# RHS_FEST22-EV_Power.net
KiCad netlist of a schematic drawn in Altium Designer
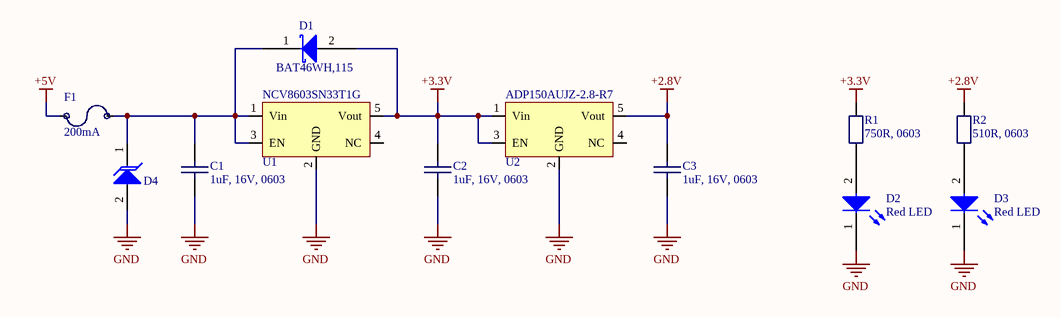
[diagram p0: RHS_FEST22-EV_Power.SchDoc]

(export (version "E")
  (design (tool "Eeschema 10.0.6"))
  (components
    (comp (ref "C1")
      (value "1uF, 16V, 0603")
      (footprint "CAP [0603] 1608")
      (fields (field (name "MANUFACTURER") "MURATA"))
      (libsource (lib "RHS_FEST22-EV_Components") (part "Cap 1uF"))
    )
    (comp (ref "C2")
      (value "1uF, 16V, 0603")
      (footprint "CAP [0603] 1608")
      (fields (field (name "MANUFACTURER") "MURATA"))
      (libsource (lib "RHS_FEST22-EV_Components") (part "Cap 1uF"))
    )
    (comp (ref "C3")
      (value "1uF, 16V, 0603")
      (footprint "CAP [0603] 1608")
      (fields (field (name "MANUFACTURER") "MURATA"))
      (libsource (lib "RHS_FEST22-EV_Components") (part "Cap 1uF"))
    )
    (comp (ref "D1")
      (value "BAT46WH,115")
      (footprint "SOD-123F")
      (description "Schottky diode")
      (fields (field (name "MANUFACTURER") "Nexperia"))
      (libsource (lib "RHS_FEST22-EV_Components") (part "BAT46WH,115"))
    )
    (comp (ref "D2")
      (value "Red LED")
      (footprint "LED [0603] 1608")
      (fields (field (name "MANUFACTURER") "KINGBRIGHT"))
      (libsource (lib "RHS_FEST22-EV_Components") (part "Red LED"))
    )
    (comp (ref "D3")
      (value "Red LED")
      (footprint "LED [0603] 1608")
      (fields (field (name "MANUFACTURER") "KINGBRIGHT"))
      (libsource (lib "RHS_FEST22-EV_Components") (part "Red LED"))
    )
    (comp (ref "D4")
      (value "TV02W5V0-G")
      (footprint "SOD-123-2")
      (description "TVS diode")
      (fields (field (name "MANUFACTURER") "Comchip"))
      (libsource (lib "RHS_FEST22-EV_Components") (part "TV02W5V0-G"))
    )
    (comp (ref "F1")
      (value "200mA")
      (footprint "RES [0603] 1608")
      (fields (field (name "MANUFACTURER") "Littlefuse"))
      (libsource (lib "RHS_FEST22-EV_Components") (part "Fuse"))
    )
    (comp (ref "R1")
      (value "750R, 0603")
      (footprint "RES [0603] 1608")
      (fields (field (name "MANUFACTURER") "YAGEO"))
      (libsource (lib "RHS_FEST22-EV_Components") (part "RES 750"))
    )
    (comp (ref "R2")
      (value "510R, 0603")
      (footprint "RES [0603] 1608")
      (fields (field (name "MANUFACTURER") "YAGEO"))
      (libsource (lib "RHS_FEST22-EV_Components") (part "Res 510"))
    )
    (comp (ref "U1")
      (value "NCV8603SN33T1G")
      (footprint "TSOT-5")
      (description "Linear voltage regulator")
      (fields (field (name "MANUFACTURER") "onsemi"))
      (libsource (lib "RHS_FEST22-EV_Components") (part "NCV8603SN33T1G"))
    )
    (comp (ref "U2")
      (value "ADP150AUJZ-2.8-R7")
      (footprint "TSOT-5")
      (description "Linear voltage regulator")
      (fields (field (name "MANUFACTURER") "Analog Devices"))
      (libsource (lib "RHS_FEST22-EV_Components") (part "ADP150AUJZ-2.8-R7"))
    )
  )
  (nets
    (net (code "1") (name "+2.8V") (class "Default")
      (node (ref "C3") (pin "1") (pinfunction "1_1") (pintype "passive"))
      (node (ref "R2") (pin "1") (pinfunction "1_1") (pintype "passive"))
      (node (ref "U2") (pin "5") (pinfunction "Vout_5") (pintype "passive"))
    )
    (net (code "2") (name "+3.3V") (class "Default")
      (node (ref "C2") (pin "1") (pinfunction "1_1") (pintype "passive"))
      (node (ref "D1") (pin "2") (pinfunction "K_2") (pintype "passive"))
      (node (ref "R1") (pin "1") (pinfunction "1_1") (pintype "passive"))
      (node (ref "U1") (pin "5") (pinfunction "Vout_5") (pintype "passive"))
      (node (ref "U2") (pin "1") (pinfunction "Vin_1") (pintype "passive"))
      (node (ref "U2") (pin "3") (pinfunction "EN_3") (pintype "passive"))
    )
    (net (code "3") (name "+5V") (class "Default") (node (ref "F1") (pin "1") (pintype "passive")))
    (net (code "4") (name "GND") (class "Default")
      (node (ref "C1") (pin "2") (pinfunction "2_2") (pintype "passive"))
      (node (ref "C2") (pin "2") (pinfunction "2_2") (pintype "passive"))
      (node (ref "C3") (pin "2") (pinfunction "2_2") (pintype "passive"))
      (node (ref "D2") (pin "1") (pinfunction "A_1") (pintype "passive"))
      (node (ref "D3") (pin "1") (pinfunction "A_1") (pintype "passive"))
      (node (ref "D4") (pin "2") (pinfunction "A_2") (pintype "passive"))
      (node (ref "U1") (pin "2") (pinfunction "GND_2") (pintype "passive"))
      (node (ref "U2") (pin "2") (pinfunction "GND_2") (pintype "passive"))
    )
    (net (code "5") (name "Net-(D1-A)") (class "Default")
      (node (ref "C1") (pin "1") (pinfunction "1_1") (pintype "passive"))
      (node (ref "D1") (pin "1") (pinfunction "A_1") (pintype "passive"))
      (node (ref "D4") (pin "1") (pinfunction "K_1") (pintype "passive"))
      (node (ref "F1") (pin "2") (pinfunction "2_2") (pintype "passive"))
      (node (ref "U1") (pin "1") (pinfunction "Vin_1") (pintype "passive"))
      (node (ref "U1") (pin "3") (pinfunction "EN_3") (pintype "passive"))
    )
    (net (code "6") (name "Net-(D2-K)") (class "Default")
      (node (ref "D2") (pin "2") (pinfunction "K_2") (pintype "passive"))
      (node (ref "R1") (pin "2") (pinfunction "2_2") (pintype "passive"))
    )
    (net (code "7") (name "Net-(D3-K)") (class "Default")
      (node (ref "D3") (pin "2") (pinfunction "K_2") (pintype "passive"))
      (node (ref "R2") (pin "2") (pinfunction "2_2") (pintype "passive"))
    )
    (net (code "8") (name "unconnected-(U1-NC-Pad4)") (class "Default")
      (node (ref "U1") (pin "4") (pinfunction "NC_4") (pintype "passive"))
    )
    (net (code "9") (name "unconnected-(U2-NC-Pad4)") (class "Default")
      (node (ref "U2") (pin "4") (pinfunction "NC_4") (pintype "passive"))
    )
  )
)
